# CSS135_continuity_board.net
KiCad netlist of a schematic drawn in Altium Designer
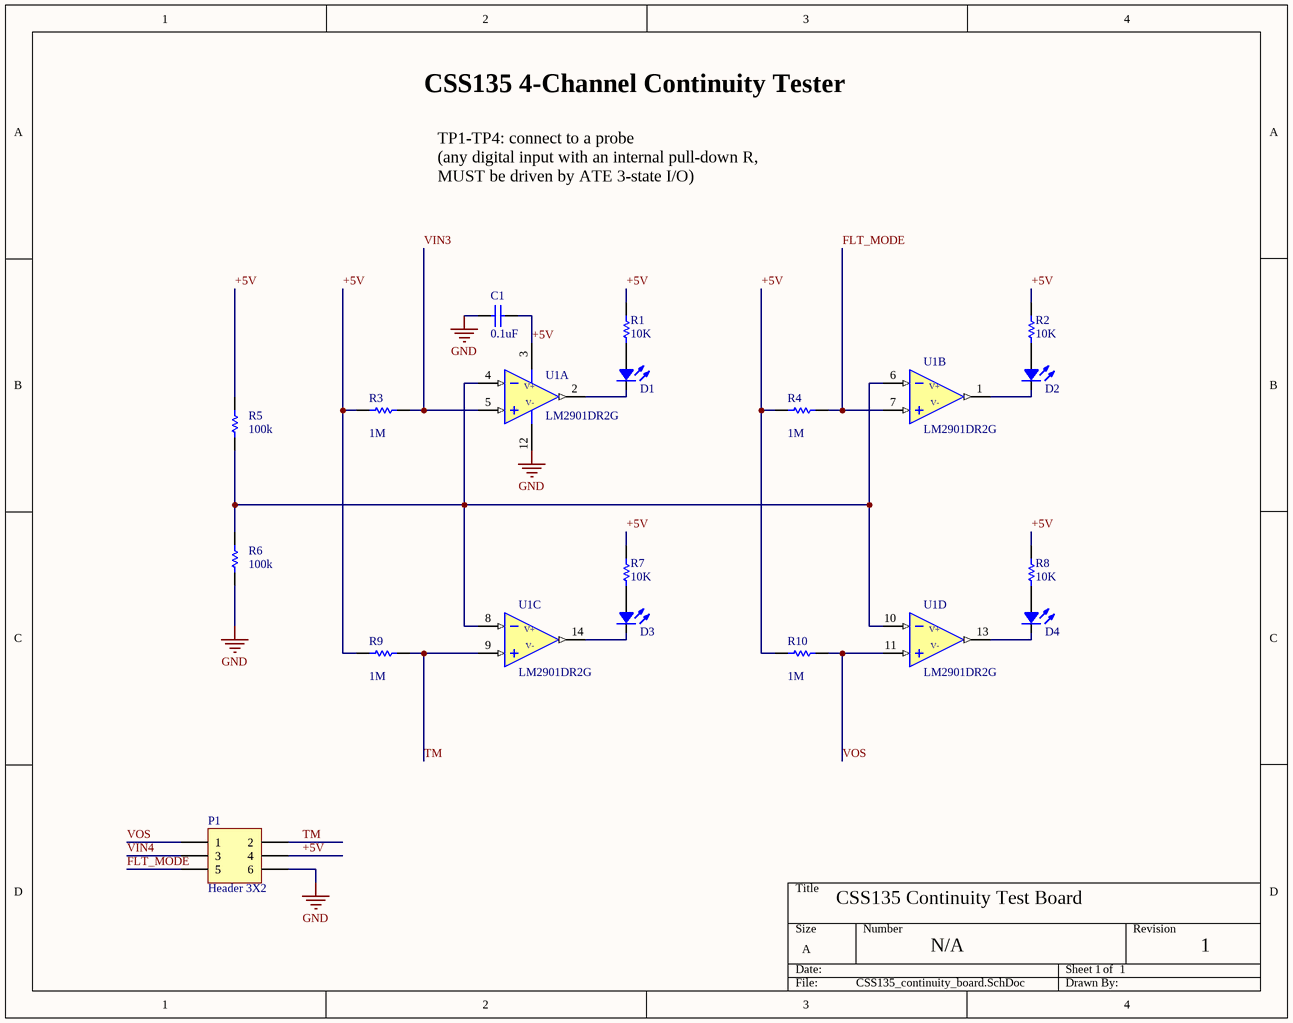
[diagram p0: CSS135_continuity_board.SchDoc]

(export (version "E")
  (design (tool "Eeschema 10.0.6"))
  (components
    (comp (ref "C1")
      (value "0.1uF")
      (footprint "0805")
      (description "CAP CER 0.1UF 50V X7R 0805")
      (fields (field (name "MANUFACTURER") "AVX Corp") (field (name "Comment") "Cap"))
      (libsource (lib "CS_symbols") (part "Cap"))
    )
    (comp (ref "D1")
      (value "LED green")
      (footprint "0805_d")
      (description "LED GREEN CLEAR 0805 SMD")
      (fields (field (name "MANUFACTURER") "Wurth Electronics Inc"))
      (libsource (lib "CS_Schlib1") (part "LED_b"))
    )
    (comp (ref "D2")
      (value "LED green")
      (footprint "0805_d")
      (description "LED GREEN CLEAR 0805 SMD")
      (fields (field (name "MANUFACTURER") "Wurth Electronics Inc"))
      (libsource (lib "CS_Schlib1") (part "LED_b"))
    )
    (comp (ref "D3")
      (value "LED green")
      (footprint "0805_d")
      (description "LED GREEN CLEAR 0805 SMD")
      (fields (field (name "MANUFACTURER") "Wurth Electronics Inc"))
      (libsource (lib "CS_Schlib1") (part "LED_b"))
    )
    (comp (ref "D4")
      (value "LED green")
      (footprint "0805_d")
      (description "LED GREEN CLEAR 0805 SMD")
      (fields (field (name "MANUFACTURER") "Wurth Electronics Inc"))
      (libsource (lib "CS_Schlib1") (part "LED_b"))
    )
    (comp (ref "P1")
      (value "Header 3X2")
      (footprint "HDR2X3")
      (description "Header, 3-Pin, Dual row")
      (fields (field (name "PUBLISHER") "Altium Limited"))
      (libsource (lib "Miscellaneous Connectors") (part "Header 3X2"))
    )
    (comp (ref "R1")
      (value "10K")
      (footprint "0603")
      (description "RES SMD 10K OHM 1% 1/10W 0603")
      (fields (field (name "MANUFACTURER") "Yageo") (field (name "Comment") "Res1"))
      (libsource (lib "CS_Schlib1") (part "Res1"))
    )
    (comp (ref "R2")
      (value "10K")
      (footprint "0603")
      (description "RES SMD 10K OHM 1% 1/10W 0603")
      (fields (field (name "MANUFACTURER") "Yageo") (field (name "Comment") "Res1"))
      (libsource (lib "CS_Schlib1") (part "Res1"))
    )
    (comp (ref "R3")
      (value "1M")
      (footprint "0805")
      (description "RES 1M OHM 1% 1/8W 0805")
      (fields (field (name "MANUFACTURER") "Stackpole"))
      (libsource (lib "CS_symbols") (part "Res1"))
    )
    (comp (ref "R4")
      (value "1M")
      (footprint "0805")
      (description "RES 1M OHM 1% 1/8W 0805")
      (fields (field (name "MANUFACTURER") "Stackpole"))
      (libsource (lib "CS_symbols") (part "Res1"))
    )
    (comp (ref "R5")
      (value "100k")
      (footprint "0805")
      (description "RES 100K OHM 1% 1/8W 0805")
      (fields (field (name "MANUFACTURER") "Stackpole"))
      (libsource (lib "CS_symbols") (part "Res1"))
    )
    (comp (ref "R6")
      (value "100k")
      (footprint "0805")
      (description "RES 100K OHM 1% 1/8W 0805")
      (fields (field (name "MANUFACTURER") "Stackpole"))
      (libsource (lib "CS_symbols") (part "Res1"))
    )
    (comp (ref "R7")
      (value "10K")
      (footprint "0603")
      (description "RES SMD 10K OHM 1% 1/10W 0603")
      (fields (field (name "MANUFACTURER") "Yageo") (field (name "Comment") "Res1"))
      (libsource (lib "CS_Schlib1") (part "Res1"))
    )
    (comp (ref "R8")
      (value "10K")
      (footprint "0603")
      (description "RES SMD 10K OHM 1% 1/10W 0603")
      (fields (field (name "MANUFACTURER") "Yageo") (field (name "Comment") "Res1"))
      (libsource (lib "CS_Schlib1") (part "Res1"))
    )
    (comp (ref "R9")
      (value "1M")
      (footprint "0805")
      (description "RES 1M OHM 1% 1/8W 0805")
      (fields (field (name "MANUFACTURER") "Stackpole"))
      (libsource (lib "CS_symbols") (part "Res1"))
    )
    (comp (ref "R10")
      (value "1M")
      (footprint "0805")
      (description "RES 1M OHM 1% 1/8W 0805")
      (fields (field (name "MANUFACTURER") "Stackpole"))
      (libsource (lib "CS_symbols") (part "Res1"))
    )
    (comp (ref "U1")
      (value "LM2901DR2G")
      (footprint "SOIC-14")
      (description "IC COMP QUAD SGL SUPPLY 14SOIC")
      (fields (field (name "MANUFACTURER") "onsemi"))
      (libsource (lib "CS_symbols") (part "LM2901"))
    )
  )
  (nets
    (net (code "1") (name "/+5V") (class "Default")
      (node (ref "C1") (pin "1") (pinfunction "1_1") (pintype "passive"))
      (node (ref "P1") (pin "4") (pinfunction "4_4") (pintype "passive"))
      (node (ref "R1") (pin "2") (pinfunction "2_2") (pintype "passive"))
      (node (ref "R10") (pin "2") (pinfunction "2_2") (pintype "passive"))
      (node (ref "R2") (pin "2") (pinfunction "2_2") (pintype "passive"))
      (node (ref "R3") (pin "2") (pinfunction "2_2") (pintype "passive"))
      (node (ref "R4") (pin "2") (pinfunction "2_2") (pintype "passive"))
      (node (ref "R5") (pin "2") (pinfunction "2_2") (pintype "passive"))
      (node (ref "R7") (pin "2") (pinfunction "2_2") (pintype "passive"))
      (node (ref "R8") (pin "2") (pinfunction "2_2") (pintype "passive"))
      (node (ref "R9") (pin "2") (pinfunction "2_2") (pintype "passive"))
      (node (ref "U1") (pin "3") (pinfunction "+VS_3") (pintype "power_in"))
    )
    (net (code "2") (name "/FLT_MODE") (class "Default")
      (node (ref "P1") (pin "5") (pinfunction "5_5") (pintype "passive"))
      (node (ref "R4") (pin "1") (pinfunction "1_1") (pintype "passive"))
      (node (ref "U1") (pin "7") (pinfunction "+IN_7") (pintype "input"))
    )
    (net (code "3") (name "/TM") (class "Default")
      (node (ref "P1") (pin "2") (pinfunction "2_2") (pintype "passive"))
      (node (ref "R9") (pin "1") (pinfunction "1_1") (pintype "passive"))
      (node (ref "U1") (pin "9") (pinfunction "+IN_9") (pintype "input"))
    )
    (net (code "4") (name "/VIN3") (class "Default")
      (node (ref "R3") (pin "1") (pinfunction "1_1") (pintype "passive"))
      (node (ref "U1") (pin "5") (pinfunction "+IN_5") (pintype "input"))
    )
    (net (code "5") (name "/VIN4") (class "Default")
      (node (ref "P1") (pin "3") (pinfunction "3_3") (pintype "passive"))
    )
    (net (code "6") (name "/VOS") (class "Default")
      (node (ref "P1") (pin "1") (pinfunction "1_1") (pintype "passive"))
      (node (ref "R10") (pin "1") (pinfunction "1_1") (pintype "passive"))
      (node (ref "U1") (pin "11") (pinfunction "+IN_11") (pintype "input"))
    )
    (net (code "7") (name "GND") (class "Default")
      (node (ref "C1") (pin "2") (pinfunction "2_2") (pintype "passive"))
      (node (ref "P1") (pin "6") (pinfunction "6_6") (pintype "passive"))
      (node (ref "R6") (pin "1") (pinfunction "1_1") (pintype "passive"))
      (node (ref "U1") (pin "12") (pinfunction "-VS_12") (pintype "power_in"))
    )
    (net (code "8") (name "Net-(D1-A)") (class "Default")
      (node (ref "D1") (pin "1") (pinfunction "A_1") (pintype "passive"))
      (node (ref "R1") (pin "1") (pinfunction "1_1") (pintype "passive"))
    )
    (net (code "9") (name "Net-(D1-K)") (class "Default")
      (node (ref "D1") (pin "2") (pinfunction "K_2") (pintype "passive"))
      (node (ref "U1") (pin "2") (pinfunction "OUT_2") (pintype "output"))
    )
    (net (code "10") (name "Net-(D2-A)") (class "Default")
      (node (ref "D2") (pin "1") (pinfunction "A_1") (pintype "passive"))
      (node (ref "R2") (pin "1") (pinfunction "1_1") (pintype "passive"))
    )
    (net (code "11") (name "Net-(D2-K)") (class "Default")
      (node (ref "D2") (pin "2") (pinfunction "K_2") (pintype "passive"))
      (node (ref "U1") (pin "1") (pinfunction "OUT_1") (pintype "output"))
    )
    (net (code "12") (name "Net-(D3-A)") (class "Default")
      (node (ref "D3") (pin "1") (pinfunction "A_1") (pintype "passive"))
      (node (ref "R7") (pin "1") (pinfunction "1_1") (pintype "passive"))
    )
    (net (code "13") (name "Net-(D3-K)") (class "Default")
      (node (ref "D3") (pin "2") (pinfunction "K_2") (pintype "passive"))
      (node (ref "U1") (pin "14") (pinfunction "OUT_14") (pintype "output"))
    )
    (net (code "14") (name "Net-(D4-A)") (class "Default")
      (node (ref "D4") (pin "1") (pinfunction "A_1") (pintype "passive"))
      (node (ref "R8") (pin "1") (pinfunction "1_1") (pintype "passive"))
    )
    (net (code "15") (name "Net-(D4-K)") (class "Default")
      (node (ref "D4") (pin "2") (pinfunction "K_2") (pintype "passive"))
      (node (ref "U1") (pin "13") (pinfunction "OUT_13") (pintype "output"))
    )
    (net (code "16") (name "Net-(U1A--IN)") (class "Default")
      (node (ref "R5") (pin "1") (pinfunction "1_1") (pintype "passive"))
      (node (ref "R6") (pin "2") (pinfunction "2_2") (pintype "passive"))
      (node (ref "U1") (pin "10") (pinfunction "-IN_10") (pintype "input"))
      (node (ref "U1") (pin "4") (pinfunction "-IN_4") (pintype "input"))
      (node (ref "U1") (pin "6") (pinfunction "-IN_6") (pintype "input"))
      (node (ref "U1") (pin "8") (pinfunction "-IN_8") (pintype "input"))
    )
  )
)
